# VRS_V1_5.net
KiCad netlist of a schematic drawn in EAGLE
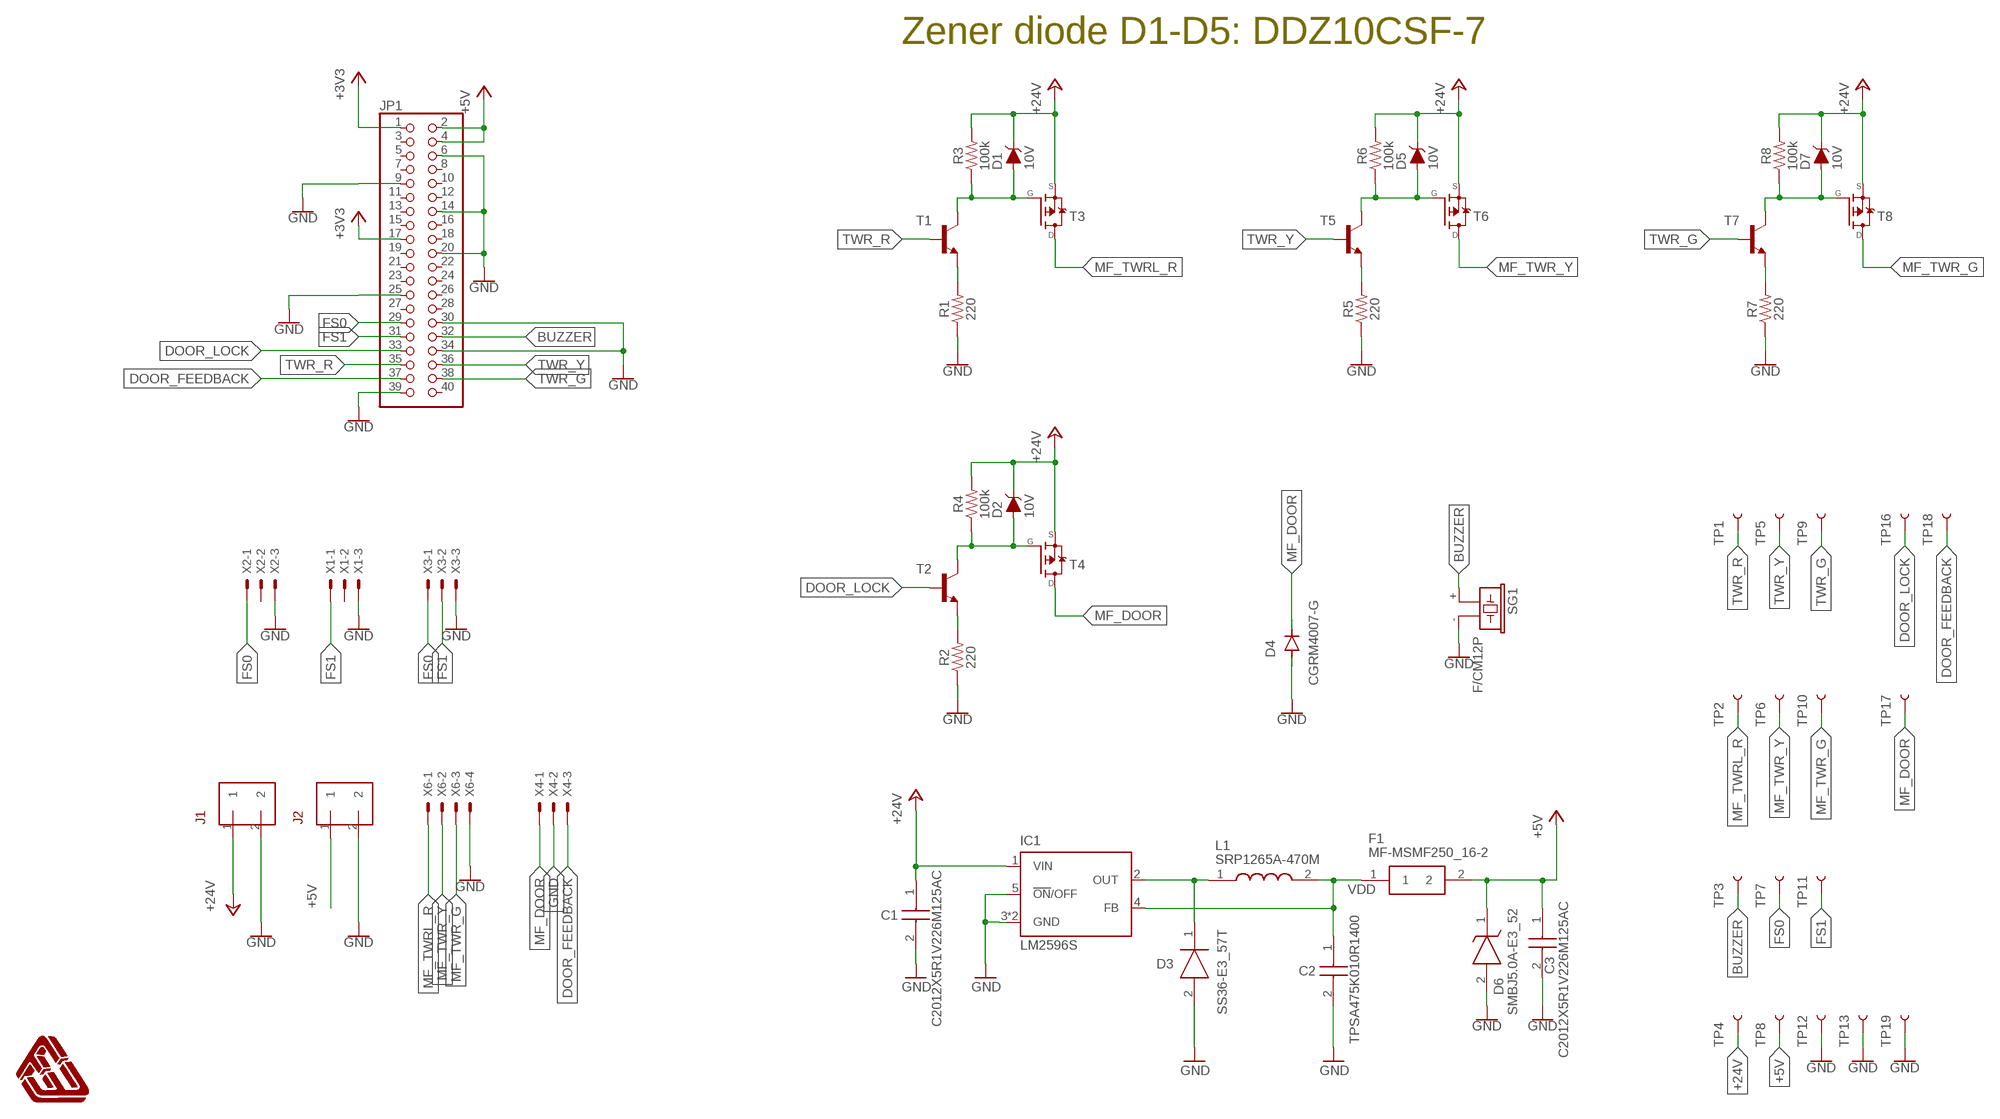
[diagram p0: schematic, sheet 1]

(export (version "E")
  (design (tool "Eeschema 10.0.6"))
  (components
    (comp (ref "C1")
      (value "C2012X5R1V226M125AC")
      (footprint "eagle-import:CAPC2012X145N")
      (fields
        (field (name "MOUSER_PART_NUMBER") "810-C2012X5R1V226MAC")
        (field (name "RS_PART_NUMBER") "9159334P")
      )
      (libsource (lib "eagle-import") (part "C2012X5R1V226M125AC"))
    )
    (comp (ref "C2")
      (value "TPSA475K010R1400")
      (footprint "eagle-import:CAPPM3216X180N")
      (fields
        (field (name "MOUSER_PART_NUMBER") "581-TPSA475K010R1400")
        (field (name "RS_PART_NUMBER") "1366129")
      )
      (libsource (lib "eagle-import") (part "TPSA475K010R1400"))
    )
    (comp (ref "C3")
      (value "C2012X5R1V226M125AC")
      (footprint "eagle-import:CAPC2012X145N")
      (fields
        (field (name "MOUSER_PART_NUMBER") "810-C2012X5R1V226MAC")
        (field (name "RS_PART_NUMBER") "9159334P")
      )
      (libsource (lib "eagle-import") (part "C2012X5R1V226M125AC"))
    )
    (comp (ref "D1")
      (value "10V")
      (footprint "eagle-import:PANASONIC_SMINI2-F5-B")
      (libsource (lib "eagle-import") (part "DIODE-ZENER-DZ2J150M0L"))
    )
    (comp (ref "D2")
      (value "10V")
      (footprint "eagle-import:PANASONIC_SMINI2-F5-B")
      (libsource (lib "eagle-import") (part "DIODE-ZENER-DZ2J150M0L"))
    )
    (comp (ref "D3")
      (value "SS36-E3_57T")
      (footprint "eagle-import:DIOM7959X262N")
      (fields
        (field (name "MANUFACTURER_PART_NUMBER") "SS36-E3/57T")
        (field (name "MOUSER_PART_NUMBER") "625-SS36-E3")
        (field (name "RS_PART_NUMBER") "7000975P")
      )
      (libsource (lib "eagle-import") (part "SS36-E3_57T"))
    )
    (comp (ref "D4")
      (value "CGRM4007-G")
      (footprint "eagle-import:SOD-123_MINI-SMA")
      (libsource (lib "eagle-import") (part "CGRM400-G7"))
    )
    (comp (ref "D5")
      (value "10V")
      (footprint "eagle-import:PANASONIC_SMINI2-F5-B")
      (libsource (lib "eagle-import") (part "DIODE-ZENER-DZ2J150M0L"))
    )
    (comp (ref "D6")
      (value "SMBJ5.0A-E3_52")
      (footprint "eagle-import:DIOM5436X244N")
      (fields
        (field (name "MANUFACTURER_PART_NUMBER") "SMBJ5.0A-E3/52")
        (field (name "MOUSER_PART_NUMBER") "625-SMBJ5.0A-E3")
        (field (name "RS_PART_NUMBER") "1652507")
      )
      (libsource (lib "eagle-import") (part "SMBJ5.0A-E3_52"))
    )
    (comp (ref "D7")
      (value "10V")
      (footprint "eagle-import:PANASONIC_SMINI2-F5-B")
      (libsource (lib "eagle-import") (part "DIODE-ZENER-DZ2J150M0L"))
    )
    (comp (ref "F1")
      (value "MF-MSMF250_16-2")
      (footprint "eagle-import:FUSC4632X160N")
      (fields
        (field (name "MANUFACTURER_PART_NUMBER") "MF-MSMF250/16-2")
        (field (name "MOUSER_PART_NUMBER") "652-MF-MSMF250/16-2")
        (field (name "RS_PART_NUMBER") "6478229P")
      )
      (libsource (lib "eagle-import") (part "MF-MSMF250_16-2"))
    )
    (comp (ref "FWLOGO_1")
      (value "FWLOGO")
      (footprint "eagle-import:FWLOGO")
      (libsource (lib "eagle-import") (part "FWLOGO"))
    )
    (comp (ref "IC1")
      (value "LM2596S")
      (footprint "eagle-import:LM2596_TO263-5")
      (fields (field (name "MF") "NATIONAL SEMICONDUCTOR") (field (name "MPN") "LM2596S-ADJ/NOPB"))
      (libsource (lib "eagle-import") (part "LM2596S"))
    )
    (comp (ref "J1")
      (value "TERMINALBLOCK/TOYO/2PIN/5MMPITCH")
      (footprint "eagle-import:TERMINALBLOCK_TOYO_2PIN_5MMPITCH")
      (libsource (lib "eagle-import") (part "TERMINALBLOCK/TOYO/2PIN/5MMPITCH"))
    )
    (comp (ref "J2")
      (value "TERMINALBLOCK/TOYO/2PIN/5MMPITCH")
      (footprint "eagle-import:TERMINALBLOCK_TOYO_2PIN_5MMPITCH")
      (libsource (lib "eagle-import") (part "TERMINALBLOCK/TOYO/2PIN/5MMPITCH"))
    )
    (comp (ref "JP1")
      (value "RASPBERRYPI_3B_GPIO")
      (footprint "eagle-import:RASPBERRYPI_3B_GPIO")
      (libsource (lib "eagle-import") (part "RASPBERRYPI_3B_GPIO"))
    )
    (comp (ref "L1")
      (value "SRP1265A-470M")
      (footprint "eagle-import:SRP1265A")
      (fields
        (field (name "MOUSER_PART_NUMBER") "652-SRP1265A-470M")
        (field (name "RS_PART_NUMBER") "8193513P")
      )
      (libsource (lib "eagle-import") (part "SRP1265A-470M"))
    )
    (comp (ref "R1")
      (value "220")
      (footprint "eagle-import:0603")
      (libsource (lib "eagle-import") (part "100KOHM-0603-1/10W-1%"))
    )
    (comp (ref "R2")
      (value "220")
      (footprint "eagle-import:0603")
      (libsource (lib "eagle-import") (part "100KOHM-0603-1/10W-1%"))
    )
    (comp (ref "R3")
      (value "100k")
      (footprint "eagle-import:0603")
      (libsource (lib "eagle-import") (part "100KOHM-0603-1/10W-1%"))
    )
    (comp (ref "R4")
      (value "100k")
      (footprint "eagle-import:0603")
      (libsource (lib "eagle-import") (part "100KOHM-0603-1/10W-1%"))
    )
    (comp (ref "R5")
      (value "220")
      (footprint "eagle-import:0603")
      (libsource (lib "eagle-import") (part "100KOHM-0603-1/10W-1%"))
    )
    (comp (ref "R6")
      (value "100k")
      (footprint "eagle-import:0603")
      (libsource (lib "eagle-import") (part "100KOHM-0603-1/10W-1%"))
    )
    (comp (ref "R7")
      (value "220")
      (footprint "eagle-import:0603")
      (libsource (lib "eagle-import") (part "100KOHM-0603-1/10W-1%"))
    )
    (comp (ref "R8")
      (value "100k")
      (footprint "eagle-import:0603")
      (libsource (lib "eagle-import") (part "100KOHM-0603-1/10W-1%"))
    )
    (comp (ref "SG1")
      (value "F/CM12P")
      (footprint "eagle-import:F_CM12P")
      (libsource (lib "eagle-import") (part "F/CM12P"))
    )
    (comp (ref "T1")
      (value "MMBT3904LT1-NPN-SOT23-BEC")
      (footprint "eagle-import:SOT23-BEC")
      (libsource (lib "eagle-import") (part "-NPN-SOT23-BECMMBT3904LT1"))
    )
    (comp (ref "T2")
      (value "MMBT3904LT1-NPN-SOT23-BEC")
      (footprint "eagle-import:SOT23-BEC")
      (libsource (lib "eagle-import") (part "-NPN-SOT23-BECMMBT3904LT1"))
    )
    (comp (ref "T3")
      (value "MOSFET_P_SOT223")
      (footprint "eagle-import:MOSFET_SOT223")
      (libsource (lib "eagle-import") (part "MOSFET_P_SOT223"))
    )
    (comp (ref "T4")
      (value "MOSFET_P_SOT223")
      (footprint "eagle-import:MOSFET_SOT223")
      (libsource (lib "eagle-import") (part "MOSFET_P_SOT223"))
    )
    (comp (ref "T5")
      (value "MMBT3904LT1-NPN-SOT23-BEC")
      (footprint "eagle-import:SOT23-BEC")
      (libsource (lib "eagle-import") (part "-NPN-SOT23-BECMMBT3904LT1"))
    )
    (comp (ref "T6")
      (value "MOSFET_P_SOT223")
      (footprint "eagle-import:MOSFET_SOT223")
      (libsource (lib "eagle-import") (part "MOSFET_P_SOT223"))
    )
    (comp (ref "T7")
      (value "MMBT3904LT1-NPN-SOT23-BEC")
      (footprint "eagle-import:SOT23-BEC")
      (libsource (lib "eagle-import") (part "-NPN-SOT23-BECMMBT3904LT1"))
    )
    (comp (ref "T8")
      (value "MOSFET_P_SOT223")
      (footprint "eagle-import:MOSFET_SOT223")
      (libsource (lib "eagle-import") (part "MOSFET_P_SOT223"))
    )
    (comp (ref "TP1")
      (value "TEST-POINT3X5")
      (footprint "eagle-import:PAD.03X.05")
      (libsource (lib "eagle-import") (part "TEST-POINT3X5"))
    )
    (comp (ref "TP2")
      (value "TEST-POINT3X5")
      (footprint "eagle-import:PAD.03X.05")
      (libsource (lib "eagle-import") (part "TEST-POINT3X5"))
    )
    (comp (ref "TP3")
      (value "TEST-POINT3X5")
      (footprint "eagle-import:PAD.03X.05")
      (libsource (lib "eagle-import") (part "TEST-POINT3X5"))
    )
    (comp (ref "TP4")
      (value "TEST-POINT3X5")
      (footprint "eagle-import:PAD.03X.05")
      (libsource (lib "eagle-import") (part "TEST-POINT3X5"))
    )
    (comp (ref "TP5")
      (value "TEST-POINT3X5")
      (footprint "eagle-import:PAD.03X.05")
      (libsource (lib "eagle-import") (part "TEST-POINT3X5"))
    )
    (comp (ref "TP6")
      (value "TEST-POINT3X5")
      (footprint "eagle-import:PAD.03X.05")
      (libsource (lib "eagle-import") (part "TEST-POINT3X5"))
    )
    (comp (ref "TP7")
      (value "TEST-POINT3X5")
      (footprint "eagle-import:PAD.03X.05")
      (libsource (lib "eagle-import") (part "TEST-POINT3X5"))
    )
    (comp (ref "TP8")
      (value "TEST-POINT3X5")
      (footprint "eagle-import:PAD.03X.05")
      (libsource (lib "eagle-import") (part "TEST-POINT3X5"))
    )
    (comp (ref "TP9")
      (value "TEST-POINT3X5")
      (footprint "eagle-import:PAD.03X.05")
      (libsource (lib "eagle-import") (part "TEST-POINT3X5"))
    )
    (comp (ref "TP10")
      (value "TEST-POINT3X5")
      (footprint "eagle-import:PAD.03X.05")
      (libsource (lib "eagle-import") (part "TEST-POINT3X5"))
    )
    (comp (ref "TP11")
      (value "TEST-POINT3X5")
      (footprint "eagle-import:PAD.03X.05")
      (libsource (lib "eagle-import") (part "TEST-POINT3X5"))
    )
    (comp (ref "TP12")
      (value "TEST-POINT3X5")
      (footprint "eagle-import:PAD.03X.05")
      (libsource (lib "eagle-import") (part "TEST-POINT3X5"))
    )
    (comp (ref "TP13")
      (value "TEST-POINT3X5")
      (footprint "eagle-import:PAD.03X.05")
      (libsource (lib "eagle-import") (part "TEST-POINT3X5"))
    )
    (comp (ref "TP16")
      (value "TEST-POINT3X5")
      (footprint "eagle-import:PAD.03X.05")
      (libsource (lib "eagle-import") (part "TEST-POINT3X5"))
    )
    (comp (ref "TP17")
      (value "TEST-POINT3X5")
      (footprint "eagle-import:PAD.03X.05")
      (libsource (lib "eagle-import") (part "TEST-POINT3X5"))
    )
    (comp (ref "TP18")
      (value "TEST-POINT3X5")
      (footprint "eagle-import:PAD.03X.05")
      (libsource (lib "eagle-import") (part "TEST-POINT3X5"))
    )
    (comp (ref "TP19")
      (value "TEST-POINT3X5")
      (footprint "eagle-import:PAD.03X.05")
      (libsource (lib "eagle-import") (part "TEST-POINT3X5"))
    )
    (comp (ref "X1")
      (value "FS1")
      (footprint "eagle-import:JST-XH-03-PACKAGE-LONG-PAD")
      (libsource (lib "eagle-import") (part "JST-XH-03-PIN-LONG-PAD"))
    )
    (comp (ref "X2")
      (value "FS0")
      (footprint "eagle-import:JST-XH-03-PACKAGE-LONG-PAD")
      (libsource (lib "eagle-import") (part "JST-XH-03-PIN-LONG-PAD"))
    )
    (comp (ref "X3")
      (value "ENCODER")
      (footprint "eagle-import:JST-XH-03-PACKAGE-LONG-PAD")
      (libsource (lib "eagle-import") (part "JST-XH-03-PIN-LONG-PAD"))
    )
    (comp (ref "X4")
      (value "DOOR LOCK")
      (footprint "eagle-import:JST-XH-03-PACKAGE-LONG-PAD")
      (libsource (lib "eagle-import") (part "JST-XH-03-PIN-LONG-PAD"))
    )
    (comp (ref "X6")
      (value "TOWER LIGHT")
      (footprint "eagle-import:JST-XH-04-PACKAGE-LONG-PAD")
      (libsource (lib "eagle-import") (part "JST-XH-04-PIN-LONG-PAD"))
    )
  )
  (nets
    (net (code "1") (name "+3V3") (class "Default")
      (node (ref "JP1") (pin "1") (pinfunction "1_1") (pintype "passive"))
      (node (ref "JP1") (pin "17") (pinfunction "17_17") (pintype "passive"))
    )
    (net (code "2") (name "+5V") (class "Default")
      (node (ref "C3") (pin "1") (pinfunction "1_1") (pintype "bidirectional"))
      (node (ref "D6") (pin "1") (pinfunction "K_1") (pintype "bidirectional"))
      (node (ref "F1") (pin "2") (pinfunction "2_2") (pintype "bidirectional"))
      (node (ref "J2") (pin "1") (pinfunction "1_1") (pintype "bidirectional"))
      (node (ref "JP1") (pin "2") (pinfunction "2_2") (pintype "passive"))
      (node (ref "JP1") (pin "4") (pinfunction "4_4") (pintype "passive"))
      (node (ref "TP8") (pin "P$1") (pinfunction "1_P$1") (pintype "bidirectional"))
    )
    (net (code "3") (name "+24V") (class "Default")
      (node (ref "C1") (pin "1") (pinfunction "1_1") (pintype "bidirectional"))
      (node (ref "D1") (pin "C") (pinfunction "C_C") (pintype "passive"))
      (node (ref "D2") (pin "C") (pinfunction "C_C") (pintype "passive"))
      (node (ref "D5") (pin "C") (pinfunction "C_C") (pintype "passive"))
      (node (ref "D7") (pin "C") (pinfunction "C_C") (pintype "passive"))
      (node (ref "IC1") (pin "1") (pinfunction "VIN_1") (pintype "input"))
      (node (ref "J1") (pin "1") (pinfunction "1_1") (pintype "bidirectional"))
      (node (ref "R3") (pin "2") (pinfunction "2_2") (pintype "passive"))
      (node (ref "R4") (pin "2") (pinfunction "2_2") (pintype "passive"))
      (node (ref "R6") (pin "2") (pinfunction "2_2") (pintype "passive"))
      (node (ref "R8") (pin "2") (pinfunction "2_2") (pintype "passive"))
      (node (ref "T3") (pin "3") (pinfunction "S_3") (pintype "passive"))
      (node (ref "T4") (pin "3") (pinfunction "S_3") (pintype "passive"))
      (node (ref "T6") (pin "3") (pinfunction "S_3") (pintype "passive"))
      (node (ref "T8") (pin "3") (pinfunction "S_3") (pintype "passive"))
      (node (ref "TP4") (pin "P$1") (pinfunction "1_P$1") (pintype "bidirectional"))
    )
    (net (code "4") (name "/VDD") (class "Default")
      (node (ref "C2") (pin "1") (pinfunction "1_1") (pintype "bidirectional"))
      (node (ref "F1") (pin "1") (pinfunction "1_1") (pintype "bidirectional"))
      (node (ref "IC1") (pin "4") (pinfunction "FB_4") (pintype "input"))
      (node (ref "L1") (pin "2") (pinfunction "2_2") (pintype "bidirectional"))
    )
    (net (code "5") (name "BUZZER") (class "Default")
      (node (ref "JP1") (pin "32") (pinfunction "32_32") (pintype "passive"))
      (node (ref "SG1") (pin "+") (pinfunction "1_+") (pintype "passive"))
      (node (ref "TP3") (pin "P$1") (pinfunction "1_P$1") (pintype "bidirectional"))
    )
    (net (code "6") (name "DOOR_FEEDBACK") (class "Default")
      (node (ref "JP1") (pin "37") (pinfunction "37_37") (pintype "passive"))
      (node (ref "TP18") (pin "P$1") (pinfunction "1_P$1") (pintype "bidirectional"))
      (node (ref "X4") (pin "3") (pinfunction "S_3") (pintype "passive"))
    )
    (net (code "7") (name "DOOR_LOCK") (class "Default")
      (node (ref "JP1") (pin "33") (pinfunction "33_33") (pintype "passive"))
      (node (ref "T2") (pin "B") (pinfunction "B_B") (pintype "passive"))
      (node (ref "TP16") (pin "P$1") (pinfunction "1_P$1") (pintype "bidirectional"))
    )
    (net (code "8") (name "FS0") (class "Default")
      (node (ref "JP1") (pin "29") (pinfunction "29_29") (pintype "passive"))
      (node (ref "TP7") (pin "P$1") (pinfunction "1_P$1") (pintype "bidirectional"))
      (node (ref "X2") (pin "1") (pinfunction "S_1") (pintype "passive"))
      (node (ref "X3") (pin "1") (pinfunction "S_1") (pintype "passive"))
    )
    (net (code "9") (name "FS1") (class "Default")
      (node (ref "JP1") (pin "31") (pinfunction "31_31") (pintype "passive"))
      (node (ref "TP11") (pin "P$1") (pinfunction "1_P$1") (pintype "bidirectional"))
      (node (ref "X1") (pin "1") (pinfunction "S_1") (pintype "passive"))
      (node (ref "X3") (pin "2") (pinfunction "S_2") (pintype "passive"))
    )
    (net (code "10") (name "GND") (class "Default")
      (node (ref "C1") (pin "2") (pinfunction "2_2") (pintype "bidirectional"))
      (node (ref "C2") (pin "2") (pinfunction "2_2") (pintype "bidirectional"))
      (node (ref "C3") (pin "2") (pinfunction "2_2") (pintype "bidirectional"))
      (node (ref "D3") (pin "2") (pinfunction "A_2") (pintype "bidirectional"))
      (node (ref "D4") (pin "A") (pinfunction "A_A") (pintype "passive"))
      (node (ref "D6") (pin "2") (pinfunction "A_2") (pintype "bidirectional"))
      (node (ref "IC1") (pin "3") (pinfunction "GND_3") (pintype "power_in"))
      (node (ref "IC1") (pin "5") (pinfunction "~{ON}/OFF_5") (pintype "input"))
      (node (ref "IC1") (pin "6") (pinfunction "GND_6") (pintype "power_in"))
      (node (ref "J1") (pin "2") (pinfunction "2_2") (pintype "bidirectional"))
      (node (ref "J2") (pin "2") (pinfunction "2_2") (pintype "bidirectional"))
      (node (ref "JP1") (pin "14") (pinfunction "14_14") (pintype "passive"))
      (node (ref "JP1") (pin "20") (pinfunction "20_20") (pintype "passive"))
      (node (ref "JP1") (pin "25") (pinfunction "25_25") (pintype "passive"))
      (node (ref "JP1") (pin "30") (pinfunction "30_30") (pintype "passive"))
      (node (ref "JP1") (pin "34") (pinfunction "34_34") (pintype "passive"))
      (node (ref "JP1") (pin "39") (pinfunction "39_39") (pintype "passive"))
      (node (ref "JP1") (pin "6") (pinfunction "6_6") (pintype "passive"))
      (node (ref "JP1") (pin "9") (pinfunction "9_9") (pintype "passive"))
      (node (ref "R1") (pin "1") (pinfunction "1_1") (pintype "passive"))
      (node (ref "R2") (pin "1") (pinfunction "1_1") (pintype "passive"))
      (node (ref "R5") (pin "1") (pinfunction "1_1") (pintype "passive"))
      (node (ref "R7") (pin "1") (pinfunction "1_1") (pintype "passive"))
      (node (ref "SG1") (pin "-") (pinfunction "2_-") (pintype "passive"))
      (node (ref "TP12") (pin "P$1") (pinfunction "1_P$1") (pintype "bidirectional"))
      (node (ref "TP13") (pin "P$1") (pinfunction "1_P$1") (pintype "bidirectional"))
      (node (ref "TP19") (pin "P$1") (pinfunction "1_P$1") (pintype "bidirectional"))
      (node (ref "X1") (pin "3") (pinfunction "S_3") (pintype "passive"))
      (node (ref "X2") (pin "3") (pinfunction "S_3") (pintype "passive"))
      (node (ref "X3") (pin "3") (pinfunction "S_3") (pintype "passive"))
      (node (ref "X4") (pin "2") (pinfunction "S_2") (pintype "passive"))
      (node (ref "X6") (pin "4") (pinfunction "S_4") (pintype "passive"))
    )
    (net (code "11") (name "MF_DOOR") (class "Default")
      (node (ref "D4") (pin "C") (pinfunction "C_C") (pintype "passive"))
      (node (ref "T4") (pin "2") (pinfunction "D_2") (pintype "passive"))
      (node (ref "T4") (pin "4") (pinfunction "D_4") (pintype "passive"))
      (node (ref "TP17") (pin "P$1") (pinfunction "1_P$1") (pintype "bidirectional"))
      (node (ref "X4") (pin "1") (pinfunction "S_1") (pintype "passive"))
    )
    (net (code "12") (name "MF_TWRL_R") (class "Default")
      (node (ref "T3") (pin "2") (pinfunction "D_2") (pintype "passive"))
      (node (ref "T3") (pin "4") (pinfunction "D_4") (pintype "passive"))
      (node (ref "TP2") (pin "P$1") (pinfunction "1_P$1") (pintype "bidirectional"))
      (node (ref "X6") (pin "1") (pinfunction "S_1") (pintype "passive"))
    )
    (net (code "13") (name "MF_TWR_G") (class "Default")
      (node (ref "T8") (pin "2") (pinfunction "D_2") (pintype "passive"))
      (node (ref "T8") (pin "4") (pinfunction "D_4") (pintype "passive"))
      (node (ref "TP10") (pin "P$1") (pinfunction "1_P$1") (pintype "bidirectional"))
      (node (ref "X6") (pin "3") (pinfunction "S_3") (pintype "passive"))
    )
    (net (code "14") (name "MF_TWR_Y") (class "Default")
      (node (ref "T6") (pin "2") (pinfunction "D_2") (pintype "passive"))
      (node (ref "T6") (pin "4") (pinfunction "D_4") (pintype "passive"))
      (node (ref "TP6") (pin "P$1") (pinfunction "1_P$1") (pintype "bidirectional"))
      (node (ref "X6") (pin "2") (pinfunction "S_2") (pintype "passive"))
    )
    (net (code "15") (name "Net-(D3-K)") (class "Default")
      (node (ref "D3") (pin "1") (pinfunction "K_1") (pintype "bidirectional"))
      (node (ref "IC1") (pin "2") (pinfunction "OUT_2") (pintype "output"))
      (node (ref "L1") (pin "1") (pinfunction "1_1") (pintype "bidirectional"))
    )
    (net (code "16") (name "Net-(R1-Pad2)") (class "Default")
      (node (ref "R1") (pin "2") (pinfunction "2_2") (pintype "passive"))
      (node (ref "T1") (pin "E") (pinfunction "E_E") (pintype "passive"))
    )
    (net (code "17") (name "Net-(R2-Pad2)") (class "Default")
      (node (ref "R2") (pin "2") (pinfunction "2_2") (pintype "passive"))
      (node (ref "T2") (pin "E") (pinfunction "E_E") (pintype "passive"))
    )
    (net (code "18") (name "Net-(R5-Pad2)") (class "Default")
      (node (ref "R5") (pin "2") (pinfunction "2_2") (pintype "passive"))
      (node (ref "T5") (pin "E") (pinfunction "E_E") (pintype "passive"))
    )
    (net (code "19") (name "Net-(R7-Pad2)") (class "Default")
      (node (ref "R7") (pin "2") (pinfunction "2_2") (pintype "passive"))
      (node (ref "T7") (pin "E") (pinfunction "E_E") (pintype "passive"))
    )
    (net (code "20") (name "Net-(T3-G)") (class "Default")
      (node (ref "D1") (pin "A") (pinfunction "A_A") (pintype "passive"))
      (node (ref "R3") (pin "1") (pinfunction "1_1") (pintype "passive"))
      (node (ref "T1") (pin "C") (pinfunction "C_C") (pintype "passive"))
      (node (ref "T3") (pin "1") (pinfunction "G_1") (pintype "passive"))
    )
    (net (code "21") (name "Net-(T4-G)") (class "Default")
      (node (ref "D2") (pin "A") (pinfunction "A_A") (pintype "passive"))
      (node (ref "R4") (pin "1") (pinfunction "1_1") (pintype "passive"))
      (node (ref "T2") (pin "C") (pinfunction "C_C") (pintype "passive"))
      (node (ref "T4") (pin "1") (pinfunction "G_1") (pintype "passive"))
    )
    (net (code "22") (name "Net-(T6-G)") (class "Default")
      (node (ref "D5") (pin "A") (pinfunction "A_A") (pintype "passive"))
      (node (ref "R6") (pin "1") (pinfunction "1_1") (pintype "passive"))
      (node (ref "T5") (pin "C") (pinfunction "C_C") (pintype "passive"))
      (node (ref "T6") (pin "1") (pinfunction "G_1") (pintype "passive"))
    )
    (net (code "23") (name "Net-(T8-G)") (class "Default")
      (node (ref "D7") (pin "A") (pinfunction "A_A") (pintype "passive"))
      (node (ref "R8") (pin "1") (pinfunction "1_1") (pintype "passive"))
      (node (ref "T7") (pin "C") (pinfunction "C_C") (pintype "passive"))
      (node (ref "T8") (pin "1") (pinfunction "G_1") (pintype "passive"))
    )
    (net (code "24") (name "TWR_G") (class "Default")
      (node (ref "JP1") (pin "38") (pinfunction "38_38") (pintype "passive"))
      (node (ref "T7") (pin "B") (pinfunction "B_B") (pintype "passive"))
      (node (ref "TP9") (pin "P$1") (pinfunction "1_P$1") (pintype "bidirectional"))
    )
    (net (code "25") (name "TWR_R") (class "Default")
      (node (ref "JP1") (pin "35") (pinfunction "35_35") (pintype "passive"))
      (node (ref "T1") (pin "B") (pinfunction "B_B") (pintype "passive"))
      (node (ref "TP1") (pin "P$1") (pinfunction "1_P$1") (pintype "bidirectional"))
    )
    (net (code "26") (name "TWR_Y") (class "Default")
      (node (ref "JP1") (pin "36") (pinfunction "36_36") (pintype "passive"))
      (node (ref "T5") (pin "B") (pinfunction "B_B") (pintype "passive"))
      (node (ref "TP5") (pin "P$1") (pinfunction "1_P$1") (pintype "bidirectional"))
    )
    (net (code "27") (name "unconnected-(JP1-Pad3)") (class "Default")
      (node (ref "JP1") (pin "3") (pinfunction "3_3") (pintype "passive"))
    )
    (net (code "28") (name "unconnected-(JP1-Pad5)") (class "Default")
      (node (ref "JP1") (pin "5") (pinfunction "5_5") (pintype "passive"))
    )
    (net (code "29") (name "unconnected-(JP1-Pad7)") (class "Default")
      (node (ref "JP1") (pin "7") (pinfunction "7_7") (pintype "passive"))
    )
    (net (code "30") (name "unconnected-(JP1-Pad8)") (class "Default")
      (node (ref "JP1") (pin "8") (pinfunction "8_8") (pintype "passive"))
    )
    (net (code "31") (name "unconnected-(JP1-Pad10)") (class "Default")
      (node (ref "JP1") (pin "10") (pinfunction "10_10") (pintype "passive"))
    )
    (net (code "32") (name "unconnected-(JP1-Pad11)") (class "Default")
      (node (ref "JP1") (pin "11") (pinfunction "11_11") (pintype "passive"))
    )
    (net (code "33") (name "unconnected-(JP1-Pad12)") (class "Default")
      (node (ref "JP1") (pin "12") (pinfunction "12_12") (pintype "passive"))
    )
    (net (code "34") (name "unconnected-(JP1-Pad13)") (class "Default")
      (node (ref "JP1") (pin "13") (pinfunction "13_13") (pintype "passive"))
    )
    (net (code "35") (name "unconnected-(JP1-Pad15)") (class "Default")
      (node (ref "JP1") (pin "15") (pinfunction "15_15") (pintype "passive"))
    )
    (net (code "36") (name "unconnected-(JP1-Pad16)") (class "Default")
      (node (ref "JP1") (pin "16") (pinfunction "16_16") (pintype "passive"))
    )
    (net (code "37") (name "unconnected-(JP1-Pad18)") (class "Default")
      (node (ref "JP1") (pin "18") (pinfunction "18_18") (pintype "passive"))
    )
    (net (code "38") (name "unconnected-(JP1-Pad19)") (class "Default")
      (node (ref "JP1") (pin "19") (pinfunction "19_19") (pintype "passive"))
    )
    (net (code "39") (name "unconnected-(JP1-Pad21)") (class "Default")
      (node (ref "JP1") (pin "21") (pinfunction "21_21") (pintype "passive"))
    )
    (net (code "40") (name "unconnected-(JP1-Pad22)") (class "Default")
      (node (ref "JP1") (pin "22") (pinfunction "22_22") (pintype "passive"))
    )
    (net (code "41") (name "unconnected-(JP1-Pad23)") (class "Default")
      (node (ref "JP1") (pin "23") (pinfunction "23_23") (pintype "passive"))
    )
    (net (code "42") (name "unconnected-(JP1-Pad24)") (class "Default")
      (node (ref "JP1") (pin "24") (pinfunction "24_24") (pintype "passive"))
    )
    (net (code "43") (name "unconnected-(JP1-Pad26)") (class "Default")
      (node (ref "JP1") (pin "26") (pinfunction "26_26") (pintype "passive"))
    )
    (net (code "44") (name "unconnected-(JP1-Pad27)") (class "Default")
      (node (ref "JP1") (pin "27") (pinfunction "27_27") (pintype "passive"))
    )
    (net (code "45") (name "unconnected-(JP1-Pad28)") (class "Default")
      (node (ref "JP1") (pin "28") (pinfunction "28_28") (pintype "passive"))
    )
    (net (code "46") (name "unconnected-(JP1-Pad40)") (class "Default")
      (node (ref "JP1") (pin "40") (pinfunction "40_40") (pintype "passive"))
    )
    (net (code "47") (name "unconnected-(X1B-S-Pad2)") (class "Default")
      (node (ref "X1") (pin "2") (pinfunction "S_2") (pintype "passive"))
    )
    (net (code "48") (name "unconnected-(X2B-S-Pad2)") (class "Default")
      (node (ref "X2") (pin "2") (pinfunction "S_2") (pintype "passive"))
    )
  )
)
